# Sensors.net
KiCad netlist of a schematic drawn in Altium Designer
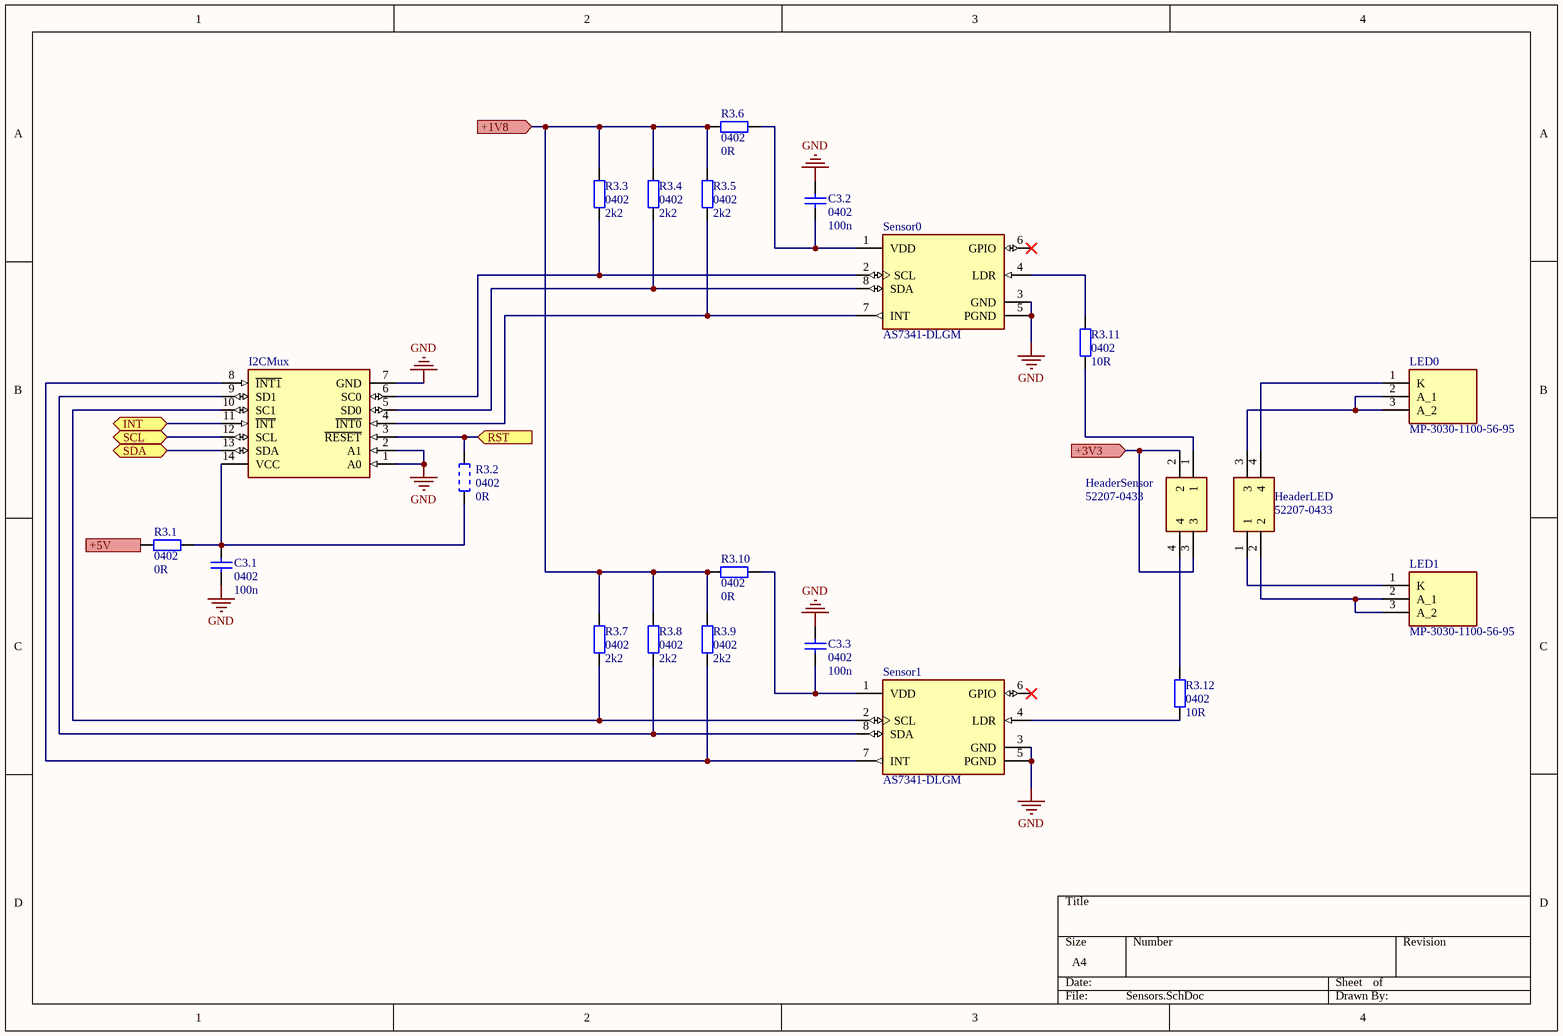
[diagram p0: Sensors.SchDoc]

(export (version "E")
  (design (tool "Eeschema 10.0.6"))
  (components
    (comp (ref "C3.1")
      (value "0402")
      (footprint "C0402_M")
      (description "Capacitor")
      (fields
        (field (name "PART NUMBER") "C0402_X5R_100n_10%")
        (field (name "ALTIUM_VALUE") "100n")
        (field (name "TOLERANCE") "10%")
      )
      (libsource (lib "LTE_altium") (part "Cap"))
    )
    (comp (ref "C3.2")
      (value "0402")
      (footprint "C0402_M")
      (description "Capacitor")
      (fields
        (field (name "PART NUMBER") "C0402_X5R_100n_10%")
        (field (name "ALTIUM_VALUE") "100n")
        (field (name "TOLERANCE") "10%")
      )
      (libsource (lib "LTE_altium") (part "Cap"))
    )
    (comp (ref "C3.3")
      (value "0402")
      (footprint "C0402_M")
      (description "Capacitor")
      (fields
        (field (name "PART NUMBER") "C0402_X5R_100n_10%")
        (field (name "ALTIUM_VALUE") "100n")
        (field (name "TOLERANCE") "10%")
      )
      (libsource (lib "LTE_altium") (part "Cap"))
    )
    (comp (ref "HeaderLED")
      (value "52207-0433")
      (footprint "SamacSys:52207-0433")
      (description "Connector")
      (fields (field (name "MOUSER PART NUMBER") "538-52207-0433"))
      (libsource (lib "*") (part "52207-0433"))
    )
    (comp (ref "HeaderSensor")
      (value "52207-0433")
      (footprint "SamacSys:52207-0433")
      (description "Connector")
      (fields (field (name "MOUSER PART NUMBER") "538-52207-0433"))
      (libsource (lib "") (part "52207-0433_1"))
    )
    (comp (ref "I2CMux")
      (value "~")
      (footprint "SamacSys:SOIC127P600X175-14N")
      (description "Integrated Circuit")
      (fields
        (field (name "MANUFACTURER_PART_NUMBER") "TCA9543ADR")
        (field (name "MOUSER PART NUMBER") "595-TCA9543ADR")
      )
      (libsource (lib "SamacSys") (part "TCA9543ADR"))
    )
    (comp (ref "LED0")
      (value "MP-3030-1100-56-95")
      (footprint "SamacSys:MP303011005780")
      (description "LED")
      (libsource (lib "*") (part "MP-3030-1100-57-80"))
    )
    (comp (ref "LED1")
      (value "MP-3030-1100-56-95")
      (footprint "SamacSys:MP303011005780")
      (description "LED")
      (libsource (lib "*") (part "MP-3030-1100-57-80"))
    )
    (comp (ref "R3.1")
      (value "0402")
      (footprint "R0402_M")
      (description "Resistor")
      (fields
        (field (name "PART NUMBER") "R0402_1%_0R")
        (field (name "ALTIUM_VALUE") "0R")
        (field (name "TOLERANCE") "1%")
      )
      (libsource (lib "") (part "Res_1"))
    )
    (comp (ref "R3.2")
      (value "0402")
      (footprint "R0402_M_open")
      (description "Resistor")
      (fields (field (name "PART NUMBER") "Res0402open") (field (name "ALTIUM_VALUE") "0R"))
      (libsource (lib "LTE_altium") (part "Res_Open"))
    )
    (comp (ref "R3.3")
      (value "0402")
      (footprint "R0402_M")
      (description "Resistor")
      (fields
        (field (name "PART NUMBER") "R0402_1%_1k")
        (field (name "ALTIUM_VALUE") "2k2")
        (field (name "TOLERANCE") "1%")
      )
      (libsource (lib "LTE_altium") (part "Res"))
    )
    (comp (ref "R3.4")
      (value "0402")
      (footprint "R0402_M")
      (description "Resistor")
      (fields
        (field (name "PART NUMBER") "R0402_1%_1k")
        (field (name "ALTIUM_VALUE") "2k2")
        (field (name "TOLERANCE") "1%")
      )
      (libsource (lib "LTE_altium") (part "Res"))
    )
    (comp (ref "R3.5")
      (value "0402")
      (footprint "R0402_M")
      (description "Resistor")
      (fields
        (field (name "PART NUMBER") "R0402_1%_1k")
        (field (name "ALTIUM_VALUE") "2k2")
        (field (name "TOLERANCE") "1%")
      )
      (libsource (lib "LTE_altium") (part "Res"))
    )
    (comp (ref "R3.6")
      (value "0402")
      (footprint "R0402_M")
      (description "Resistor")
      (fields
        (field (name "PART NUMBER") "R0402_0R")
        (field (name "ALTIUM_VALUE") "0R")
        (field (name "TOLERANCE") "1%")
      )
      (libsource (lib "") (part "Res_1"))
    )
    (comp (ref "R3.7")
      (value "0402")
      (footprint "R0402_M")
      (description "Resistor")
      (fields
        (field (name "PART NUMBER") "R0402_1%_1k")
        (field (name "ALTIUM_VALUE") "2k2")
        (field (name "TOLERANCE") "1%")
      )
      (libsource (lib "LTE_altium") (part "Res"))
    )
    (comp (ref "R3.8")
      (value "0402")
      (footprint "R0402_M")
      (description "Resistor")
      (fields
        (field (name "PART NUMBER") "R0402_1%_1k")
        (field (name "ALTIUM_VALUE") "2k2")
        (field (name "TOLERANCE") "1%")
      )
      (libsource (lib "LTE_altium") (part "Res"))
    )
    (comp (ref "R3.9")
      (value "0402")
      (footprint "R0402_M")
      (description "Resistor")
      (fields
        (field (name "PART NUMBER") "R0402_1%_1k")
        (field (name "ALTIUM_VALUE") "2k2")
        (field (name "TOLERANCE") "1%")
      )
      (libsource (lib "LTE_altium") (part "Res"))
    )
    (comp (ref "R3.10")
      (value "0402")
      (footprint "R0402_M")
      (description "Resistor")
      (fields
        (field (name "PART NUMBER") "R0402_0R")
        (field (name "ALTIUM_VALUE") "0R")
        (field (name "TOLERANCE") "1%")
      )
      (libsource (lib "") (part "Res_1"))
    )
    (comp (ref "R3.11")
      (value "0402")
      (footprint "R0402_M")
      (description "Resistor")
      (fields
        (field (name "PART NUMBER") "R0402_1%_100R")
        (field (name "ALTIUM_VALUE") "10R")
        (field (name "TOLERANCE") "1%")
      )
      (libsource (lib "LTE_altium") (part "Res"))
    )
    (comp (ref "R3.12")
      (value "0402")
      (footprint "R0402_M")
      (description "Resistor")
      (fields
        (field (name "PART NUMBER") "R0402_1%_100R")
        (field (name "ALTIUM_VALUE") "10R")
        (field (name "TOLERANCE") "1%")
      )
      (libsource (lib "LTE_altium") (part "Res"))
    )
    (comp (ref "Sensor0")
      (value "AS7341-DLGM")
      (footprint "FP-AS7341-DLGM-MFG")
      (description "SENSOR AMBIENT LIGHT")
      (libsource (lib "Altium Content Vault") (part "fbda4f44316dd9d70da80813f013d10"))
    )
    (comp (ref "Sensor1")
      (value "AS7341-DLGM")
      (footprint "FP-AS7341-DLGM-MFG")
      (description "SENSOR AMBIENT LIGHT")
      (libsource (lib "Altium Content Vault") (part "fbda4f44316dd9d70da80813f013d10"))
    )
  )
  (nets
    (net (code "1") (name "/+1V8") (class "Default")
      (node (ref "R3.10") (pin "1") (pinfunction "1_1") (pintype "passive"))
      (node (ref "R3.3") (pin "2") (pinfunction "2_2") (pintype "passive"))
      (node (ref "R3.4") (pin "2") (pinfunction "2_2") (pintype "passive"))
      (node (ref "R3.5") (pin "2") (pinfunction "2_2") (pintype "passive"))
      (node (ref "R3.6") (pin "1") (pinfunction "1_1") (pintype "passive"))
      (node (ref "R3.7") (pin "2") (pinfunction "2_2") (pintype "passive"))
      (node (ref "R3.8") (pin "2") (pinfunction "2_2") (pintype "passive"))
      (node (ref "R3.9") (pin "2") (pinfunction "2_2") (pintype "passive"))
    )
    (net (code "2") (name "/+3V3") (class "Default")
      (node (ref "HeaderSensor") (pin "2") (pinfunction "2_2") (pintype "passive"))
      (node (ref "HeaderSensor") (pin "3") (pinfunction "3_3") (pintype "passive"))
    )
    (net (code "3") (name "/+5V") (class "Default")
      (node (ref "R3.1") (pin "1") (pinfunction "1_1") (pintype "passive"))
    )
    (net (code "4") (name "/INT") (class "Default")
      (node (ref "I2CMux") (pin "11") (pinfunction "~{INT}_11") (pintype "input"))
    )
    (net (code "5") (name "/RST") (class "Default")
      (node (ref "I2CMux") (pin "3") (pinfunction "~{RESET}_3") (pintype "input"))
      (node (ref "R3.2") (pin "2") (pinfunction "2_2") (pintype "passive"))
    )
    (net (code "6") (name "/SCL") (class "Default")
      (node (ref "I2CMux") (pin "12") (pinfunction "SCL_12") (pintype "bidirectional"))
    )
    (net (code "7") (name "/SDA") (class "Default")
      (node (ref "I2CMux") (pin "13") (pinfunction "SDA_13") (pintype "bidirectional"))
    )
    (net (code "8") (name "GND") (class "Default")
      (node (ref "C3.1") (pin "1") (pinfunction "1_1") (pintype "passive"))
      (node (ref "C3.2") (pin "2") (pinfunction "2_2") (pintype "passive"))
      (node (ref "C3.3") (pin "2") (pinfunction "2_2") (pintype "passive"))
      (node (ref "I2CMux") (pin "1") (pinfunction "A0_1") (pintype "input"))
      (node (ref "I2CMux") (pin "2") (pinfunction "A1_2") (pintype "input"))
      (node (ref "I2CMux") (pin "7") (pinfunction "GND_7") (pintype "power_in"))
      (node (ref "Sensor0") (pin "3") (pinfunction "GND_3") (pintype "power_in"))
      (node (ref "Sensor0") (pin "5") (pinfunction "PGND_5") (pintype "power_in"))
      (node (ref "Sensor1") (pin "3") (pinfunction "GND_3") (pintype "power_in"))
      (node (ref "Sensor1") (pin "5") (pinfunction "PGND_5") (pintype "power_in"))
    )
    (net (code "9") (name "Net-(HeaderSensor-Pad1)") (class "Default")
      (node (ref "HeaderSensor") (pin "1") (pinfunction "1_1") (pintype "passive"))
      (node (ref "R3.11") (pin "1") (pinfunction "1_1") (pintype "passive"))
    )
    (net (code "10") (name "Net-(HeaderSensor-Pad4)") (class "Default")
      (node (ref "HeaderSensor") (pin "4") (pinfunction "4_4") (pintype "passive"))
      (node (ref "R3.12") (pin "2") (pinfunction "2_2") (pintype "passive"))
    )
    (net (code "11") (name "Net-(I2CMux-SC0)") (class "Default")
      (node (ref "I2CMux") (pin "6") (pinfunction "SC0_6") (pintype "bidirectional"))
      (node (ref "R3.3") (pin "1") (pinfunction "1_1") (pintype "passive"))
      (node (ref "Sensor0") (pin "2") (pinfunction "SCL_2") (pintype "bidirectional"))
    )
    (net (code "12") (name "Net-(I2CMux-SC1)") (class "Default")
      (node (ref "I2CMux") (pin "10") (pinfunction "SC1_10") (pintype "bidirectional"))
      (node (ref "R3.7") (pin "1") (pinfunction "1_1") (pintype "passive"))
      (node (ref "Sensor1") (pin "2") (pinfunction "SCL_2") (pintype "bidirectional"))
    )
    (net (code "13") (name "Net-(I2CMux-SD0)") (class "Default")
      (node (ref "I2CMux") (pin "5") (pinfunction "SD0_5") (pintype "bidirectional"))
      (node (ref "R3.4") (pin "1") (pinfunction "1_1") (pintype "passive"))
      (node (ref "Sensor0") (pin "8") (pinfunction "SDA_8") (pintype "bidirectional"))
    )
    (net (code "14") (name "Net-(I2CMux-SD1)") (class "Default")
      (node (ref "I2CMux") (pin "9") (pinfunction "SD1_9") (pintype "bidirectional"))
      (node (ref "R3.8") (pin "1") (pinfunction "1_1") (pintype "passive"))
      (node (ref "Sensor1") (pin "8") (pinfunction "SDA_8") (pintype "bidirectional"))
    )
    (net (code "15") (name "Net-(I2CMux-VCC)") (class "Default")
      (node (ref "C3.1") (pin "2") (pinfunction "2_2") (pintype "passive"))
      (node (ref "I2CMux") (pin "14") (pinfunction "VCC_14") (pintype "power_in"))
      (node (ref "R3.1") (pin "2") (pinfunction "2_2") (pintype "passive"))
      (node (ref "R3.2") (pin "1") (pinfunction "1_1") (pintype "passive"))
    )
    (net (code "16") (name "Net-(I2CMux-~{INT0})") (class "Default")
      (node (ref "I2CMux") (pin "4") (pinfunction "~{INT0}_4") (pintype "input"))
      (node (ref "R3.5") (pin "1") (pinfunction "1_1") (pintype "passive"))
      (node (ref "Sensor0") (pin "7") (pinfunction "INT_7") (pintype "output"))
    )
    (net (code "17") (name "Net-(I2CMux-~{INT1})") (class "Default")
      (node (ref "I2CMux") (pin "8") (pinfunction "~{INT1}_8") (pintype "input"))
      (node (ref "R3.9") (pin "1") (pinfunction "1_1") (pintype "passive"))
      (node (ref "Sensor1") (pin "7") (pinfunction "INT_7") (pintype "output"))
    )
    (net (code "18") (name "Net-(LED0-A_1)") (class "Default")
      (node (ref "HeaderLED") (pin "3") (pinfunction "3_3") (pintype "passive"))
      (node (ref "LED0") (pin "2") (pinfunction "A_1_2") (pintype "passive"))
      (node (ref "LED0") (pin "3") (pinfunction "A_2_3") (pintype "passive"))
    )
    (net (code "19") (name "Net-(LED0-K)") (class "Default")
      (node (ref "HeaderLED") (pin "4") (pinfunction "4_4") (pintype "passive"))
      (node (ref "LED0") (pin "1") (pinfunction "K_1") (pintype "passive"))
    )
    (net (code "20") (name "Net-(LED1-A_1)") (class "Default")
      (node (ref "HeaderLED") (pin "2") (pinfunction "2_2") (pintype "passive"))
      (node (ref "LED1") (pin "2") (pinfunction "A_1_2") (pintype "passive"))
      (node (ref "LED1") (pin "3") (pinfunction "A_2_3") (pintype "passive"))
    )
    (net (code "21") (name "Net-(LED1-K)") (class "Default")
      (node (ref "HeaderLED") (pin "1") (pinfunction "1_1") (pintype "passive"))
      (node (ref "LED1") (pin "1") (pinfunction "K_1") (pintype "passive"))
    )
    (net (code "22") (name "Net-(Sensor0-LDR)") (class "Default")
      (node (ref "R3.11") (pin "2") (pinfunction "2_2") (pintype "passive"))
      (node (ref "Sensor0") (pin "4") (pinfunction "LDR_4") (pintype "input"))
    )
    (net (code "23") (name "Net-(Sensor0-VDD)") (class "Default")
      (node (ref "C3.2") (pin "1") (pinfunction "1_1") (pintype "passive"))
      (node (ref "R3.6") (pin "2") (pinfunction "2_2") (pintype "passive"))
      (node (ref "Sensor0") (pin "1") (pinfunction "VDD_1") (pintype "power_in"))
    )
    (net (code "24") (name "Net-(Sensor1-LDR)") (class "Default")
      (node (ref "R3.12") (pin "1") (pinfunction "1_1") (pintype "passive"))
      (node (ref "Sensor1") (pin "4") (pinfunction "LDR_4") (pintype "input"))
    )
    (net (code "25") (name "Net-(Sensor1-VDD)") (class "Default")
      (node (ref "C3.3") (pin "1") (pinfunction "1_1") (pintype "passive"))
      (node (ref "R3.10") (pin "2") (pinfunction "2_2") (pintype "passive"))
      (node (ref "Sensor1") (pin "1") (pinfunction "VDD_1") (pintype "power_in"))
    )
    (net (code "26") (name "unconnected-(Sensor0-GPIO-Pad6)") (class "Default")
      (node (ref "Sensor0") (pin "6") (pinfunction "GPIO_6") (pintype "bidirectional+no_connect"))
    )
    (net (code "27") (name "unconnected-(Sensor1-GPIO-Pad6)") (class "Default")
      (node (ref "Sensor1") (pin "6") (pinfunction "GPIO_6") (pintype "bidirectional+no_connect"))
    )
  )
)
